# wt12_uart_breakout_board_v12.net
KiCad netlist of a schematic drawn in EAGLE
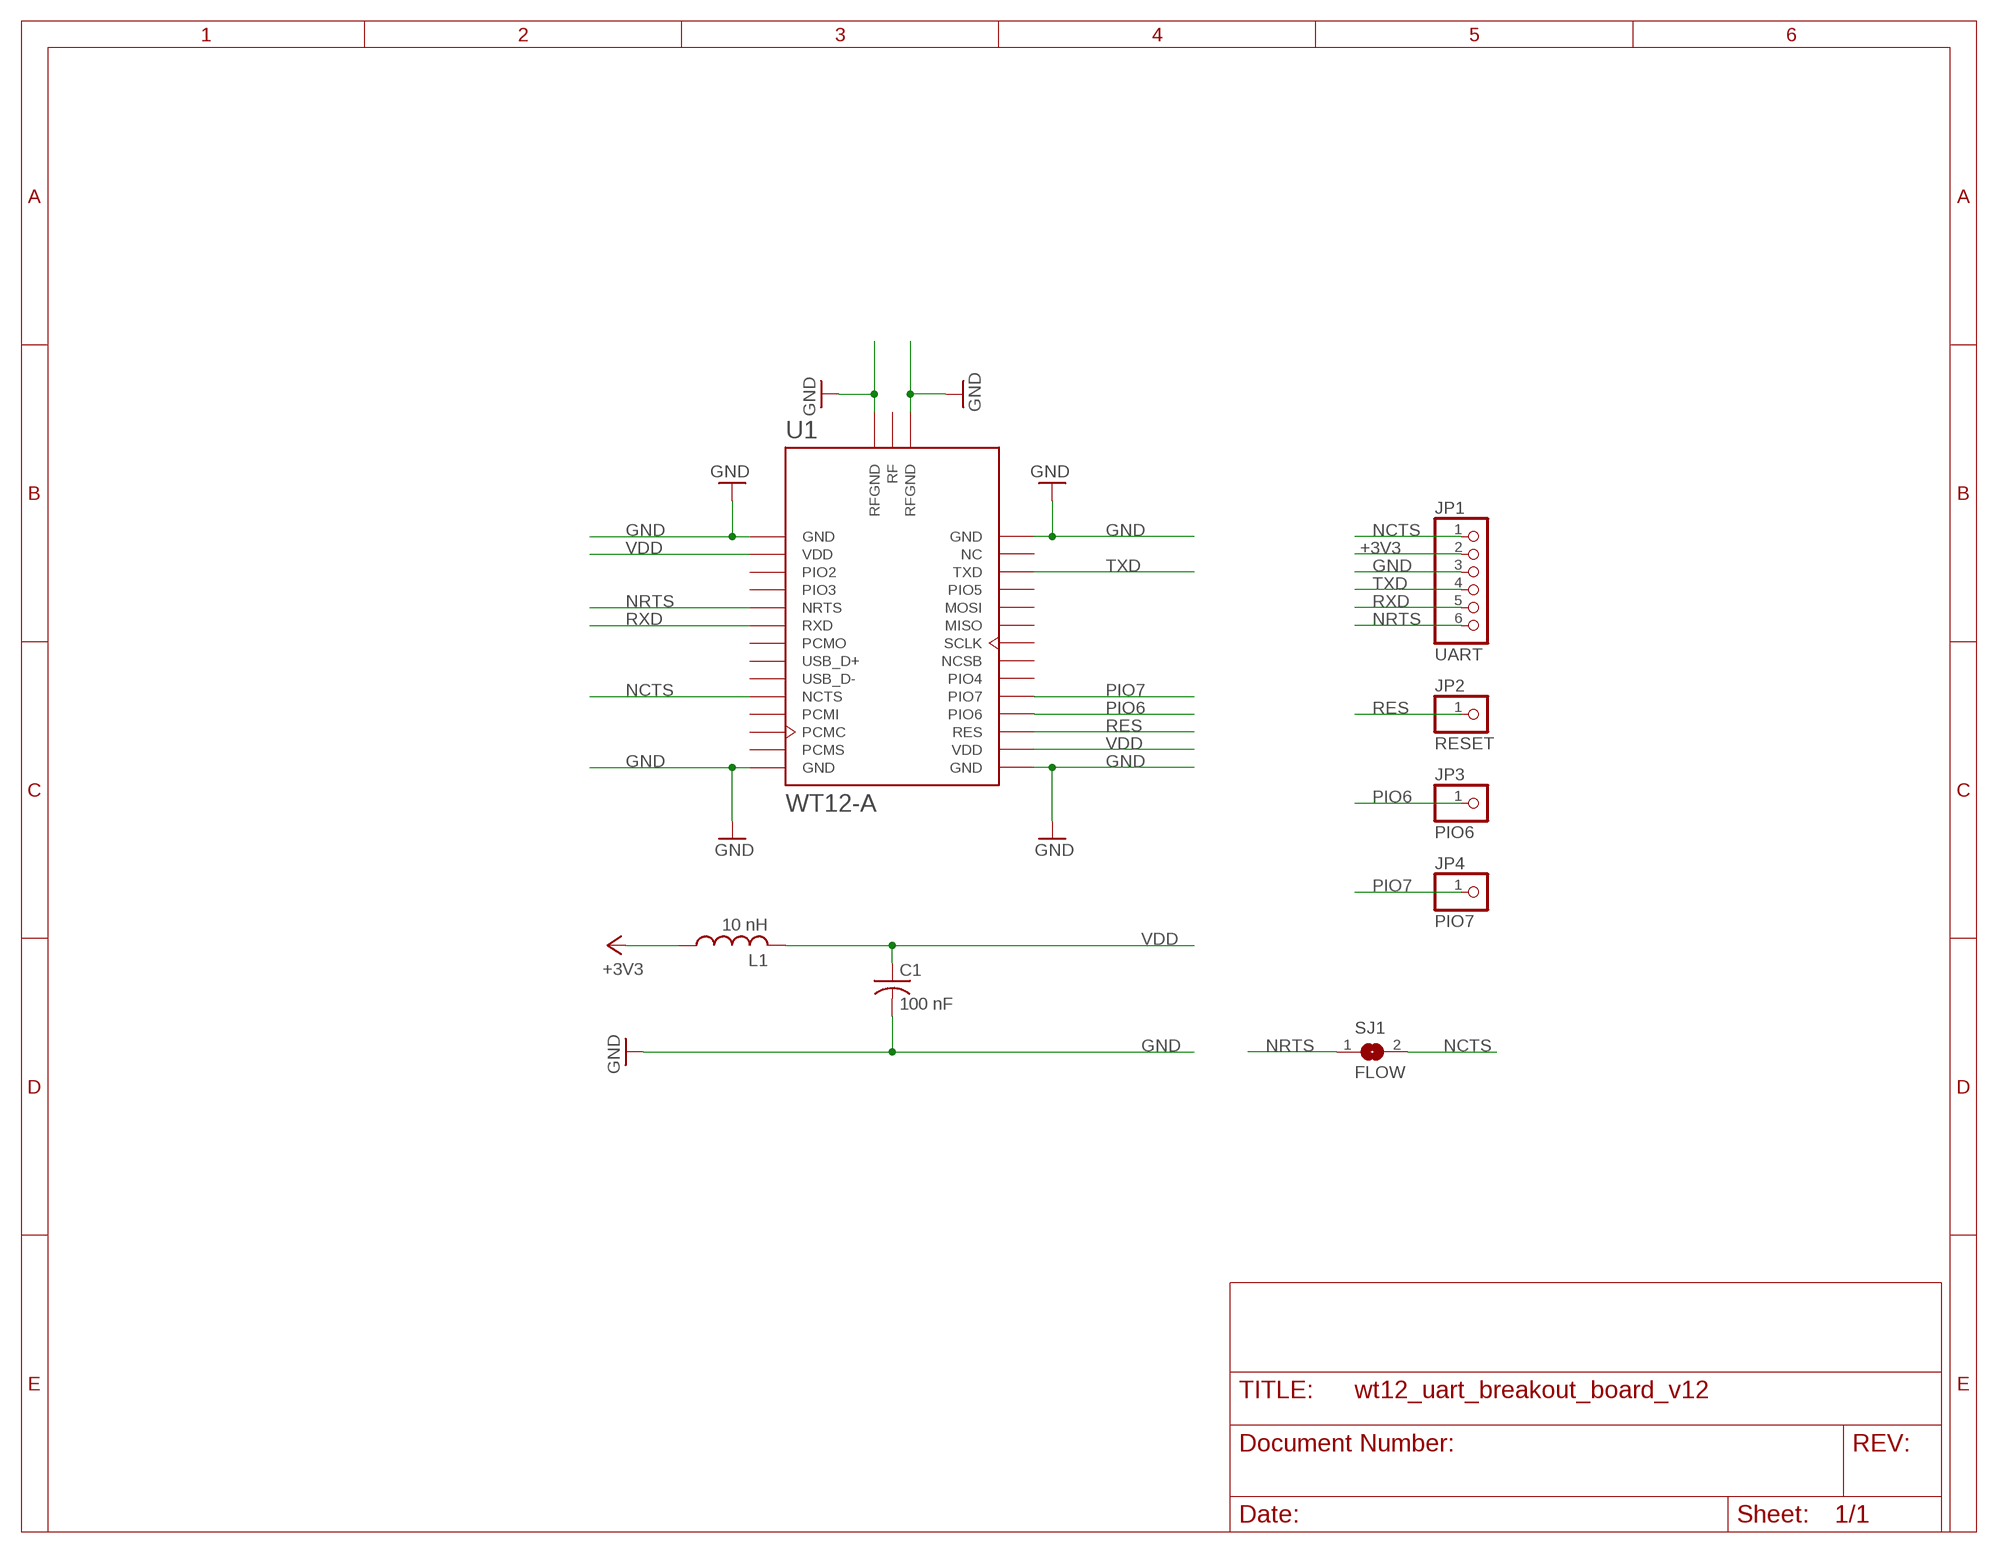
[diagram p0: schematic, sheet 1]

(export (version "E")
  (design (tool "Eeschema 10.0.6"))
  (components
    (comp (ref "C1")
      (value "100 nF")
      (footprint "eagle-import:C0603K")
      (libsource (lib "eagle-import") (part "C-USC0603K"))
    )
    (comp (ref "JP1")
      (value "UART")
      (footprint "eagle-import:1X06")
      (libsource (lib "eagle-import") (part "PINHD-1X6"))
    )
    (comp (ref "JP2")
      (value "RESET")
      (footprint "eagle-import:1X01")
      (libsource (lib "eagle-import") (part "PINHD-1X1"))
    )
    (comp (ref "JP3")
      (value "PIO6")
      (footprint "eagle-import:1X01")
      (libsource (lib "eagle-import") (part "PINHD-1X1"))
    )
    (comp (ref "JP4")
      (value "PIO7")
      (footprint "eagle-import:1X01")
      (libsource (lib "eagle-import") (part "PINHD-1X1"))
    )
    (comp (ref "L1")
      (value "10 nH")
      (footprint "eagle-import:L2012C")
      (libsource (lib "eagle-import") (part "L-USL2012C"))
    )
    (comp (ref "SJ1")
      (value "FLOW")
      (footprint "eagle-import:SJ")
      (libsource (lib "eagle-import") (part "SJ"))
    )
    (comp (ref "U1")
      (value "WT12-A")
      (footprint "eagle-import:WT12-A")
      (libsource (lib "eagle-import") (part "WT12-A-VISUAL"))
    )
  )
  (nets
    (net (code "1") (name "+3V3") (class "Default")
      (node (ref "JP1") (pin "2") (pinfunction "2_2") (pintype "passive"))
      (node (ref "L1") (pin "1") (pinfunction "1_1") (pintype "passive"))
    )
    (net (code "2") (name "/NCTS") (class "Default")
      (node (ref "JP1") (pin "1") (pinfunction "1_1") (pintype "passive"))
      (node (ref "SJ1") (pin "2") (pinfunction "2_2") (pintype "passive"))
      (node (ref "U1") (pin "NCTS") (pinfunction "NCTS_NCTS") (pintype "input"))
    )
    (net (code "3") (name "/NRTS") (class "Default")
      (node (ref "JP1") (pin "6") (pinfunction "6_6") (pintype "passive"))
      (node (ref "SJ1") (pin "1") (pinfunction "1_1") (pintype "passive"))
      (node (ref "U1") (pin "NRTS") (pinfunction "NRTS_NRTS") (pintype "output"))
    )
    (net (code "4") (name "/PIO6") (class "Default")
      (node (ref "JP3") (pin "1") (pinfunction "1_1") (pintype "passive"))
      (node (ref "U1") (pin "PIO6") (pinfunction "PIO6_PIO6") (pintype "bidirectional"))
    )
    (net (code "5") (name "/PIO7") (class "Default")
      (node (ref "JP4") (pin "1") (pinfunction "1_1") (pintype "passive"))
      (node (ref "U1") (pin "PIO7") (pinfunction "PIO7_PIO7") (pintype "bidirectional"))
    )
    (net (code "6") (name "/RES") (class "Default")
      (node (ref "JP2") (pin "1") (pinfunction "1_1") (pintype "passive"))
      (node (ref "U1") (pin "RES") (pinfunction "RES_RES") (pintype "input"))
    )
    (net (code "7") (name "/RXD") (class "Default")
      (node (ref "JP1") (pin "5") (pinfunction "5_5") (pintype "passive"))
      (node (ref "U1") (pin "RXD") (pinfunction "RXD_RXD") (pintype "input"))
    )
    (net (code "8") (name "/TXD") (class "Default")
      (node (ref "JP1") (pin "4") (pinfunction "4_4") (pintype "passive"))
      (node (ref "U1") (pin "TXD") (pinfunction "TXD_TXD") (pintype "output"))
    )
    (net (code "9") (name "/VDD") (class "Default")
      (node (ref "C1") (pin "1") (pinfunction "1_1") (pintype "passive"))
      (node (ref "L1") (pin "2") (pinfunction "2_2") (pintype "passive"))
      (node (ref "U1") (pin "VDD1") (pinfunction "VDD_VDD1") (pintype "power_in"))
      (node (ref "U1") (pin "VDD2") (pinfunction "VDD_VDD2") (pintype "power_in"))
    )
    (net (code "10") (name "GND") (class "Default")
      (node (ref "C1") (pin "2") (pinfunction "2_2") (pintype "passive"))
      (node (ref "JP1") (pin "3") (pinfunction "3_3") (pintype "passive"))
      (node (ref "U1") (pin "GND1") (pinfunction "GND_GND1") (pintype "power_in"))
      (node (ref "U1") (pin "GND2") (pinfunction "GND_GND2") (pintype "power_in"))
      (node (ref "U1") (pin "GND3") (pinfunction "GND_GND3") (pintype "power_in"))
      (node (ref "U1") (pin "GND4") (pinfunction "GND_GND4") (pintype "power_in"))
      (node (ref "U1") (pin "RFGND1") (pinfunction "RFGND_RFGND1") (pintype "bidirectional"))
      (node (ref "U1") (pin "RFGND2") (pinfunction "RFGND_RFGND2") (pintype "bidirectional"))
    )
    (net (code "11") (name "unconnected-(U1-PadMISO)") (class "Default")
      (node (ref "U1") (pin "MISO") (pinfunction "MISO_MISO") (pintype "output"))
    )
    (net (code "12") (name "unconnected-(U1-PadMOSI)") (class "Default")
      (node (ref "U1") (pin "MOSI") (pinfunction "MOSI_MOSI") (pintype "input"))
    )
    (net (code "13") (name "unconnected-(U1-PadNC)") (class "Default")
      (node (ref "U1") (pin "NC") (pinfunction "NC_NC") (pintype "no_connect"))
    )
    (net (code "14") (name "unconnected-(U1-PadNCSB)") (class "Default")
      (node (ref "U1") (pin "NCSB") (pinfunction "NCSB_NCSB") (pintype "input"))
    )
    (net (code "15") (name "unconnected-(U1-PadPCMC)") (class "Default")
      (node (ref "U1") (pin "PCMC") (pinfunction "PCMC_PCMC") (pintype "bidirectional"))
    )
    (net (code "16") (name "unconnected-(U1-PadPCMI)") (class "Default")
      (node (ref "U1") (pin "PCMI") (pinfunction "PCMI_PCMI") (pintype "input"))
    )
    (net (code "17") (name "unconnected-(U1-PadPCMO)") (class "Default")
      (node (ref "U1") (pin "PCMO") (pinfunction "PCMO_PCMO") (pintype "output"))
    )
    (net (code "18") (name "unconnected-(U1-PadPCMS)") (class "Default")
      (node (ref "U1") (pin "PCMS") (pinfunction "PCMS_PCMS") (pintype "bidirectional"))
    )
    (net (code "19") (name "unconnected-(U1-PadPIO2)") (class "Default")
      (node (ref "U1") (pin "PIO2") (pinfunction "PIO2_PIO2") (pintype "bidirectional"))
    )
    (net (code "20") (name "unconnected-(U1-PadPIO3)") (class "Default")
      (node (ref "U1") (pin "PIO3") (pinfunction "PIO3_PIO3") (pintype "bidirectional"))
    )
    (net (code "21") (name "unconnected-(U1-PadPIO4)") (class "Default")
      (node (ref "U1") (pin "PIO4") (pinfunction "PIO4_PIO4") (pintype "bidirectional"))
    )
    (net (code "22") (name "unconnected-(U1-PadPIO5)") (class "Default")
      (node (ref "U1") (pin "PIO5") (pinfunction "PIO5_PIO5") (pintype "bidirectional"))
    )
    (net (code "23") (name "unconnected-(U1-PadRF)") (class "Default")
      (node (ref "U1") (pin "RF") (pinfunction "RF_RF") (pintype "bidirectional"))
    )
    (net (code "24") (name "unconnected-(U1-PadSCLK)") (class "Default")
      (node (ref "U1") (pin "SCLK") (pinfunction "SCLK_SCLK") (pintype "input"))
    )
    (net (code "25") (name "unconnected-(U1-PadUSB_D+)") (class "Default")
      (node (ref "U1") (pin "USB_D+") (pinfunction "USB_D+_USB_D+") (pintype "bidirectional"))
    )
    (net (code "26") (name "unconnected-(U1-PadUSB_D-)") (class "Default")
      (node (ref "U1") (pin "USB_D-") (pinfunction "USB_D-_USB_D-") (pintype "bidirectional"))
    )
  )
)
